# RadationTestBoardMCU.net
KiCad netlist of a schematic drawn in Altium Designer
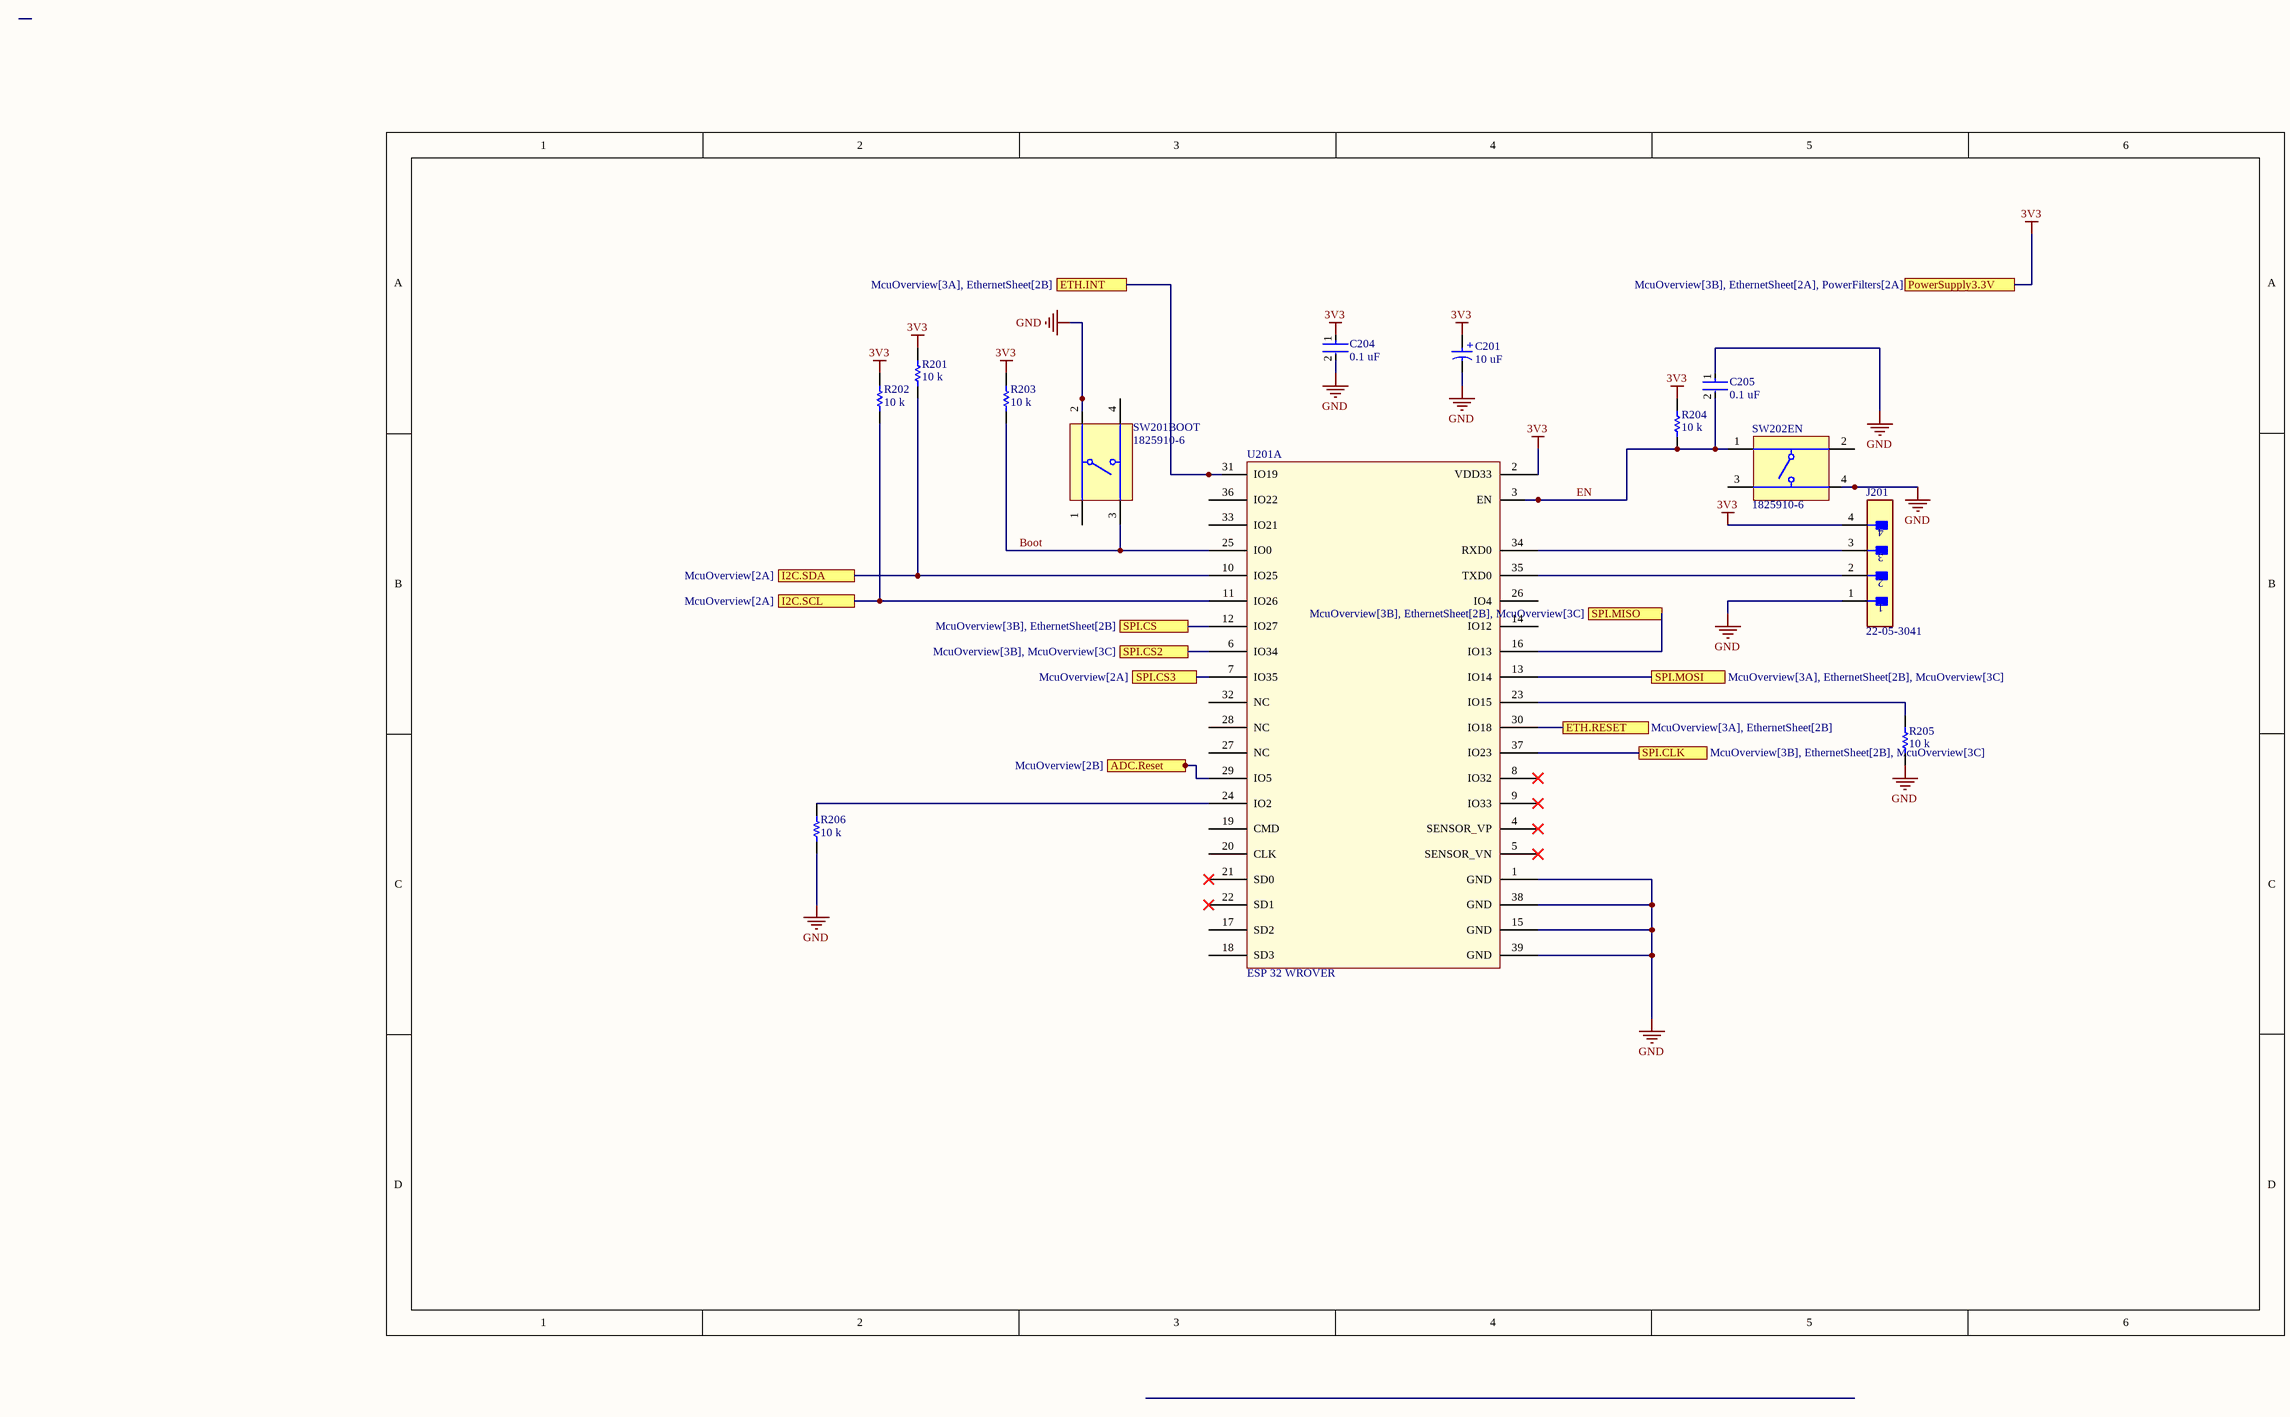
[diagram p0: RadationTestBoardMCU.SchDoc]

(export (version "E")
  (design (tool "Eeschema 10.0.6"))
  (components
    (comp (ref "C201")
      (value "10 uF")
      (footprint "WCAP-HTG5_D6.3H8")
      (description "870575873001 Cap, 10Uf, 63V, Alu Elec, Hybrid, Rad Rohs Compliant: Yes 870575873001")
      (libsource (lib "Altium Content Vault") (part "Capacitor_Polarized"))
    )
    (comp (ref "C204")
      (value "0.1 uF")
      (footprint "FP-CC0603-DA-IPC_A")
      (description "CAP CER 0.1UF 50V X7R 0603 CC0603JRX7R9BB104")
      (fields (field (name "TOLERANCE") "5%"))
      (libsource (lib "Altium Content Vault") (part "02cd4be3c70576c341d710602a673aa"))
    )
    (comp (ref "C205")
      (value "0.1 uF")
      (footprint "FP-CC0603-DA-IPC_A")
      (description "CAP CER 0.1UF 50V X7R 0603 CC0603JRX7R9BB104")
      (fields (field (name "TOLERANCE") "5%"))
      (libsource (lib "Altium Content Vault") (part "02cd4be3c70576c341d710602a673aa"))
    )
    (comp (ref "J201")
      (value "22-05-3041")
      (footprint "FP-22-05-3041-MFG")
      (description "CONN HEADER R/A 4POS 2.54MM")
      (fields
        (field (name "OCTOPART") "https://octopart.com/22-05-3041-molex-2579")
        (field (name "MANUFACTURER") "Molex")
      )
      (libsource (lib "Altium Content Vault") (part "299a8cea1bdcbc3624fe62c390fa72c"))
    )
    (comp (ref "R201")
      (value "10 k")
      (footprint "RESC2013X60X35NL10T20")
      (fields (field (name "MANUFACTURER") "Yageo"))
      (libsource (lib "Altium Content Vault") (part "RES-2"))
    )
    (comp (ref "R202")
      (value "10 k")
      (footprint "RESC2013X60X35NL10T20")
      (fields (field (name "MANUFACTURER") "Yageo"))
      (libsource (lib "Altium Content Vault") (part "RES-2"))
    )
    (comp (ref "R203")
      (value "10 k")
      (footprint "RESC2013X60X35NL10T20")
      (fields (field (name "MANUFACTURER") "Yageo"))
      (libsource (lib "Altium Content Vault") (part "RES-2"))
    )
    (comp (ref "R204")
      (value "10 k")
      (footprint "RESC2013X60X35NL10T20")
      (fields (field (name "MANUFACTURER") "Yageo"))
      (libsource (lib "Altium Content Vault") (part "RES-2"))
    )
    (comp (ref "R205")
      (value "10 k")
      (footprint "RESC2013X60X35NL10T20")
      (fields (field (name "MANUFACTURER") "Yageo"))
      (libsource (lib "Altium Content Vault") (part "RES-2"))
    )
    (comp (ref "R206")
      (value "10 k")
      (footprint "RESC2013X60X35NL10T20")
      (fields (field (name "MANUFACTURER") "Yageo"))
      (libsource (lib "Altium Content Vault") (part "RES-2"))
    )
    (comp (ref "SW201BOOT")
      (value "1825910-6")
      (footprint "TECO-1825910-6_V")
      (description "Tact Switch, SPST-NO, 0.05 A, -35 to 85 degC, 4-Pin THD, RoHS, Bulk")
      (fields (field (name "MANUFACTURER") "TE Connectivity"))
      (libsource (lib "") (part "SW-SPST-4_A_1"))
    )
    (comp (ref "SW202EN")
      (value "1825910-6")
      (footprint "TECO-1825910-6_V")
      (description "Tact Switch, SPST-NO, 0.05 A, -35 to 85 degC, 4-Pin THD, RoHS, Bulk")
      (fields (field (name "MANUFACTURER") "TE Connectivity"))
      (libsource (lib "Altium Content Vault") (part "SW-SPST-4_A"))
    )
    (comp (ref "U201")
      (value "ESP 32 WROVER")
      (footprint "PCBComponent_1")
      (libsource (lib "RadiationTextBoard") (part "ESP 32 WROVER"))
    )
  )
  (nets
    (net (code "1") (name "/ADC.Reset") (class "Default")
      (node (ref "U201") (pin "29") (pinfunction "IO5_29") (pintype "passive"))
    )
    (net (code "2") (name "/Boot") (class "Default")
      (node (ref "R203") (pin "1") (pinfunction "1_1") (pintype "passive"))
      (node (ref "SW201BOOT") (pin "3") (pinfunction "3_3") (pintype "passive"))
      (node (ref "U201") (pin "25") (pinfunction "IO0_25") (pintype "passive"))
    )
    (net (code "3") (name "/EN") (class "Default")
      (node (ref "C205") (pin "2") (pinfunction "2_2") (pintype "passive"))
      (node (ref "R204") (pin "1") (pinfunction "1_1") (pintype "passive"))
      (node (ref "SW202EN") (pin "1") (pinfunction "1_1") (pintype "passive"))
      (node (ref "U201") (pin "3") (pinfunction "EN_3") (pintype "passive"))
    )
    (net (code "4") (name "/ETH.INT") (class "Default")
      (node (ref "U201") (pin "31") (pinfunction "IO19_31") (pintype "passive"))
    )
    (net (code "5") (name "/ETH.RESET") (class "Default")
      (node (ref "U201") (pin "30") (pinfunction "IO18_30") (pintype "passive"))
    )
    (net (code "6") (name "/I2C.SCL") (class "Default")
      (node (ref "R202") (pin "1") (pinfunction "1_1") (pintype "passive"))
      (node (ref "U201") (pin "11") (pinfunction "IO26_11") (pintype "passive"))
    )
    (net (code "7") (name "/I2C.SDA") (class "Default")
      (node (ref "R201") (pin "1") (pinfunction "1_1") (pintype "passive"))
      (node (ref "U201") (pin "10") (pinfunction "IO25_10") (pintype "passive"))
    )
    (net (code "8") (name "/SPI.CLK") (class "Default")
      (node (ref "U201") (pin "37") (pinfunction "IO23_37") (pintype "passive"))
    )
    (net (code "9") (name "/SPI.CS") (class "Default")
      (node (ref "U201") (pin "12") (pinfunction "IO27_12") (pintype "passive"))
    )
    (net (code "10") (name "/SPI.CS2") (class "Default")
      (node (ref "U201") (pin "6") (pinfunction "IO34_6") (pintype "passive"))
    )
    (net (code "11") (name "/SPI.CS3") (class "Default")
      (node (ref "U201") (pin "7") (pinfunction "IO35_7") (pintype "passive"))
    )
    (net (code "12") (name "/SPI.MISO") (class "Default")
      (node (ref "U201") (pin "16") (pinfunction "IO13_16") (pintype "passive"))
    )
    (net (code "13") (name "/SPI.MOSI") (class "Default")
      (node (ref "U201") (pin "13") (pinfunction "IO14_13") (pintype "passive"))
    )
    (net (code "14") (name "3V3") (class "Default")
      (node (ref "C201") (pin "1") (pinfunction "P_1") (pintype "passive"))
      (node (ref "C204") (pin "1") (pinfunction "1_1") (pintype "passive"))
      (node (ref "J201") (pin "4") (pinfunction "4_4") (pintype "passive"))
      (node (ref "R201") (pin "2") (pinfunction "2_2") (pintype "passive"))
      (node (ref "R202") (pin "2") (pinfunction "2_2") (pintype "passive"))
      (node (ref "R203") (pin "2") (pinfunction "2_2") (pintype "passive"))
      (node (ref "R204") (pin "2") (pinfunction "2_2") (pintype "passive"))
      (node (ref "U201") (pin "2") (pinfunction "VDD33_2") (pintype "passive"))
    )
    (net (code "15") (name "GND") (class "Default")
      (node (ref "C201") (pin "2") (pinfunction "N_2") (pintype "passive"))
      (node (ref "C204") (pin "2") (pinfunction "2_2") (pintype "passive"))
      (node (ref "C205") (pin "1") (pinfunction "1_1") (pintype "passive"))
      (node (ref "J201") (pin "1") (pinfunction "1_1") (pintype "passive"))
      (node (ref "R205") (pin "1") (pinfunction "1_1") (pintype "passive"))
      (node (ref "R206") (pin "1") (pinfunction "1_1") (pintype "passive"))
      (node (ref "SW201BOOT") (pin "2") (pinfunction "2_2") (pintype "passive"))
      (node (ref "SW202EN") (pin "4") (pinfunction "4_4") (pintype "passive"))
      (node (ref "U201") (pin "1") (pinfunction "GND_1") (pintype "passive"))
      (node (ref "U201") (pin "15") (pinfunction "GND_15") (pintype "passive"))
      (node (ref "U201") (pin "38") (pinfunction "GND_38") (pintype "passive"))
      (node (ref "U201") (pin "39") (pinfunction "GND_39") (pintype "passive"))
    )
    (net (code "16") (name "Net-(U201-IO2)") (class "Default")
      (node (ref "R206") (pin "2") (pinfunction "2_2") (pintype "passive"))
      (node (ref "U201") (pin "24") (pinfunction "IO2_24") (pintype "passive"))
    )
    (net (code "17") (name "Net-(U201-IO15)") (class "Default")
      (node (ref "R205") (pin "2") (pinfunction "2_2") (pintype "passive"))
      (node (ref "U201") (pin "23") (pinfunction "IO15_23") (pintype "passive"))
    )
    (net (code "18") (name "Net-(U201-RXD0)") (class "Default")
      (node (ref "J201") (pin "3") (pinfunction "3_3") (pintype "passive"))
      (node (ref "U201") (pin "34") (pinfunction "RXD0_34") (pintype "passive"))
    )
    (net (code "19") (name "Net-(U201-TXD0)") (class "Default")
      (node (ref "J201") (pin "2") (pinfunction "2_2") (pintype "passive"))
      (node (ref "U201") (pin "35") (pinfunction "TXD0_35") (pintype "passive"))
    )
    (net (code "20") (name "unconnected-(SW201BOOT-Pad1)") (class "Default")
      (node (ref "SW201BOOT") (pin "1") (pinfunction "1_1") (pintype "passive"))
    )
    (net (code "21") (name "unconnected-(SW201BOOT-Pad4)") (class "Default")
      (node (ref "SW201BOOT") (pin "4") (pinfunction "4_4") (pintype "passive"))
    )
    (net (code "22") (name "unconnected-(SW202EN-Pad2)") (class "Default")
      (node (ref "SW202EN") (pin "2") (pinfunction "2_2") (pintype "passive"))
    )
    (net (code "23") (name "unconnected-(SW202EN-Pad3)") (class "Default")
      (node (ref "SW202EN") (pin "3") (pinfunction "3_3") (pintype "passive"))
    )
    (net (code "24") (name "unconnected-(U201-CLK-Pad20)") (class "Default")
      (node (ref "U201") (pin "20") (pinfunction "CLK_20") (pintype "passive"))
    )
    (net (code "25") (name "unconnected-(U201-CMD-Pad19)") (class "Default")
      (node (ref "U201") (pin "19") (pinfunction "CMD_19") (pintype "passive"))
    )
    (net (code "26") (name "unconnected-(U201-IO4-Pad26)") (class "Default")
      (node (ref "U201") (pin "26") (pinfunction "IO4_26") (pintype "passive"))
    )
    (net (code "27") (name "unconnected-(U201-IO12-Pad14)") (class "Default")
      (node (ref "U201") (pin "14") (pinfunction "IO12_14") (pintype "passive"))
    )
    (net (code "28") (name "unconnected-(U201-IO21-Pad33)") (class "Default")
      (node (ref "U201") (pin "33") (pinfunction "IO21_33") (pintype "passive"))
    )
    (net (code "29") (name "unconnected-(U201-IO22-Pad36)") (class "Default")
      (node (ref "U201") (pin "36") (pinfunction "IO22_36") (pintype "passive"))
    )
    (net (code "30") (name "unconnected-(U201-IO32-Pad8)") (class "Default")
      (node (ref "U201") (pin "8") (pinfunction "IO32_8") (pintype "passive+no_connect"))
    )
    (net (code "31") (name "unconnected-(U201-IO33-Pad9)") (class "Default")
      (node (ref "U201") (pin "9") (pinfunction "IO33_9") (pintype "passive+no_connect"))
    )
    (net (code "32") (name "unconnected-(U201-NC-Pad27)") (class "Default")
      (node (ref "U201") (pin "27") (pinfunction "NC_27") (pintype "passive"))
    )
    (net (code "33") (name "unconnected-(U201-NC-Pad28)") (class "Default")
      (node (ref "U201") (pin "28") (pinfunction "NC_28") (pintype "passive"))
    )
    (net (code "34") (name "unconnected-(U201-NC-Pad32)") (class "Default")
      (node (ref "U201") (pin "32") (pinfunction "NC_32") (pintype "passive"))
    )
    (net (code "35") (name "unconnected-(U201-SD0-Pad21)") (class "Default")
      (node (ref "U201") (pin "21") (pinfunction "SD0_21") (pintype "passive+no_connect"))
    )
    (net (code "36") (name "unconnected-(U201-SD1-Pad22)") (class "Default")
      (node (ref "U201") (pin "22") (pinfunction "SD1_22") (pintype "passive+no_connect"))
    )
    (net (code "37") (name "unconnected-(U201-SD2-Pad17)") (class "Default")
      (node (ref "U201") (pin "17") (pinfunction "SD2_17") (pintype "passive"))
    )
    (net (code "38") (name "unconnected-(U201-SD3-Pad18)") (class "Default")
      (node (ref "U201") (pin "18") (pinfunction "SD3_18") (pintype "passive"))
    )
    (net (code "39") (name "unconnected-(U201-SENSOR_VN-Pad5)") (class "Default")
      (node (ref "U201") (pin "5") (pinfunction "SENSOR_VN_5") (pintype "passive+no_connect"))
    )
    (net (code "40") (name "unconnected-(U201-SENSOR_VP-Pad4)") (class "Default")
      (node (ref "U201") (pin "4") (pinfunction "SENSOR_VP_4") (pintype "passive+no_connect"))
    )
  )
)
